# polarshield3_0e.net
KiCad netlist of a schematic drawn in EAGLE
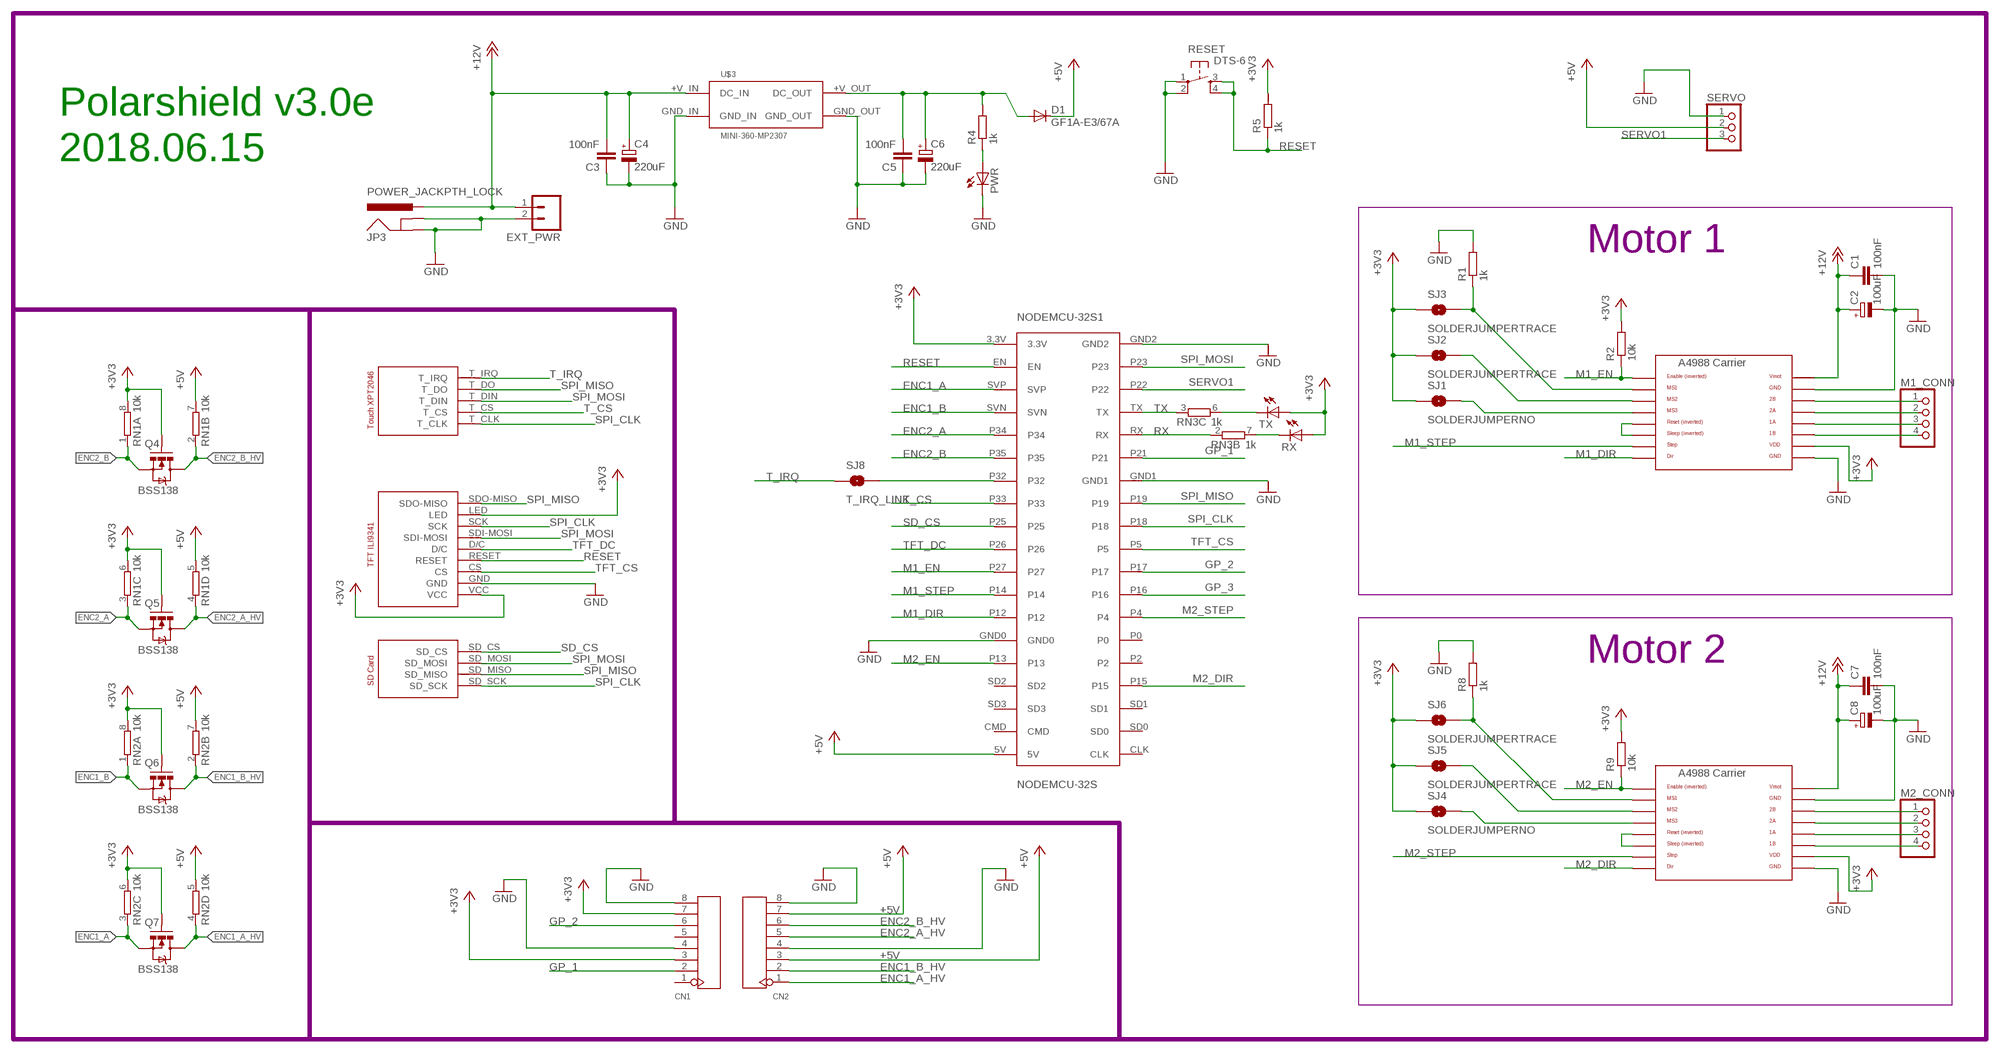
[diagram p0: schematic, sheet 1]

(export (version "E")
  (design (tool "Eeschema 10.0.6"))
  (components
    (comp (ref "C1")
      (value "100nF")
      (footprint "eagle-import:C0805")
      (libsource (lib "eagle-import") (part "C-EUC0805"))
    )
    (comp (ref "C2")
      (value "100uF")
      (footprint "eagle-import:153CLV-0605")
      (libsource (lib "eagle-import") (part "CPOL-EU153CLV-0605"))
    )
    (comp (ref "C3")
      (value "100nF")
      (footprint "eagle-import:C0805")
      (libsource (lib "eagle-import") (part "C-EUC0805"))
    )
    (comp (ref "C4")
      (value "220uF")
      (footprint "eagle-import:153CLV-0605")
      (libsource (lib "eagle-import") (part "CPOL-EU153CLV-0605"))
    )
    (comp (ref "C5")
      (value "100nF")
      (footprint "eagle-import:C0805")
      (libsource (lib "eagle-import") (part "C-EUC0805"))
    )
    (comp (ref "C6")
      (value "220uF")
      (footprint "eagle-import:153CLV-0605")
      (libsource (lib "eagle-import") (part "CPOL-EU153CLV-0605"))
    )
    (comp (ref "C7")
      (value "100nF")
      (footprint "eagle-import:C0805")
      (libsource (lib "eagle-import") (part "C-EUC0805"))
    )
    (comp (ref "C8")
      (value "100uF")
      (footprint "eagle-import:153CLV-0605")
      (libsource (lib "eagle-import") (part "CPOL-EU153CLV-0605"))
    )
    (comp (ref "CN1")
      (value "DIP-BLACK-FEMALE-HEADER-VERT(8P-2.54)")
      (footprint "eagle-import:H8-2.54")
      (fields (field (name "MPN") "F185-1108A1BSYC1"))
      (libsource (lib "eagle-import") (part "DIP-BLACK-FEMALE-HEADER-VERT(8P-2.54)"))
    )
    (comp (ref "CN2")
      (value "DIP-BLACK-FEMALE-HEADER-VERT(8P-2.54)")
      (footprint "eagle-import:H8-2.54")
      (fields (field (name "MPN") "F185-1108A1BSYC1"))
      (libsource (lib "eagle-import") (part "DIP-BLACK-FEMALE-HEADER-VERT(8P-2.54)"))
    )
    (comp (ref "D1")
      (value "GF1A-E3/67A")
      (footprint "eagle-import:DO214BA")
      (libsource (lib "eagle-import") (part "DIODE-DO214BA"))
    )
    (comp (ref "EXT_PWR")
      (value "M02PTH")
      (footprint "eagle-import:1X02")
      (libsource (lib "eagle-import") (part "M02PTH"))
    )
    (comp (ref "JP3")
      (value "POWER_JACKPTH_LOCK")
      (footprint "eagle-import:POWER_JACK_PTH_LOCK")
      (libsource (lib "eagle-import") (part "POWER_JACKPTH_LOCK"))
    )
    (comp (ref "M1_CONN")
      (value "PINHD-1X4/90")
      (footprint "eagle-import:1X04_90")
      (libsource (lib "eagle-import") (part "PINHD-1X4/90"))
    )
    (comp (ref "M2_CONN")
      (value "PINHD-1X4/90")
      (footprint "eagle-import:1X04_90")
      (libsource (lib "eagle-import") (part "PINHD-1X4/90"))
    )
    (comp (ref "MOTOR_1")
      (value "A4988BREAKOUT")
      (footprint "eagle-import:A4988BREAKOUT")
      (libsource (lib "eagle-import") (part "A4988BREAKOUT"))
    )
    (comp (ref "MOTOR_2")
      (value "A4988BREAKOUT")
      (footprint "eagle-import:A4988BREAKOUT")
      (libsource (lib "eagle-import") (part "A4988BREAKOUT"))
    )
    (comp (ref "NODEMCU-32S1")
      (value "NODEMCU-32S")
      (footprint "eagle-import:NODEMCU-32S")
      (libsource (lib "eagle-import") (part "NODEMCU-32S"))
    )
    (comp (ref "PWR")
      (value "LEDCHIPLED_0805")
      (footprint "eagle-import:CHIPLED_0805")
      (libsource (lib "eagle-import") (part "LEDCHIPLED_0805"))
    )
    (comp (ref "Q4")
      (value "BSS138")
      (footprint "eagle-import:SOT23-3")
      (libsource (lib "eagle-import") (part "MOSFET-NCHANNELSMD"))
    )
    (comp (ref "Q5")
      (value "BSS138")
      (footprint "eagle-import:SOT23-3")
      (libsource (lib "eagle-import") (part "MOSFET-NCHANNELSMD"))
    )
    (comp (ref "Q6")
      (value "BSS138")
      (footprint "eagle-import:SOT23-3")
      (libsource (lib "eagle-import") (part "MOSFET-NCHANNELSMD"))
    )
    (comp (ref "Q7")
      (value "BSS138")
      (footprint "eagle-import:SOT23-3")
      (libsource (lib "eagle-import") (part "MOSFET-NCHANNELSMD"))
    )
    (comp (ref "R1")
      (value "1k")
      (footprint "eagle-import:M0805")
      (libsource (lib "eagle-import") (part "R-EU_M0805"))
    )
    (comp (ref "R2")
      (value "10k")
      (footprint "eagle-import:M0805")
      (libsource (lib "eagle-import") (part "R-EU_M0805"))
    )
    (comp (ref "R4")
      (value "1k")
      (footprint "eagle-import:M0805")
      (libsource (lib "eagle-import") (part "R-EU_M0805"))
    )
    (comp (ref "R5")
      (value "1k")
      (footprint "eagle-import:M0805")
      (libsource (lib "eagle-import") (part "R-EU_M0805"))
    )
    (comp (ref "R8")
      (value "1k")
      (footprint "eagle-import:M0805")
      (libsource (lib "eagle-import") (part "R-EU_M0805"))
    )
    (comp (ref "R9")
      (value "10k")
      (footprint "eagle-import:M0805")
      (libsource (lib "eagle-import") (part "R-EU_M0805"))
    )
    (comp (ref "RESET")
      (value "DTS-6")
      (footprint "eagle-import:DTS-6")
      (libsource (lib "eagle-import") (part "DTS-6"))
    )
    (comp (ref "RN1")
      (value "10k")
      (footprint "eagle-import:EXB38V")
      (libsource (lib "eagle-import") (part "4R-NEXB38V"))
    )
    (comp (ref "RN2")
      (value "10k")
      (footprint "eagle-import:EXB38V")
      (libsource (lib "eagle-import") (part "4R-NEXB38V"))
    )
    (comp (ref "RN3")
      (value "1k")
      (footprint "eagle-import:EXB38V")
      (libsource (lib "eagle-import") (part "4R-NEXB38V"))
    )
    (comp (ref "RX")
      (value "LEDCHIPLED_0805")
      (footprint "eagle-import:CHIPLED_0805")
      (libsource (lib "eagle-import") (part "LEDCHIPLED_0805"))
    )
    (comp (ref "SERVO")
      (value "PINHD-1X3/90")
      (footprint "eagle-import:1X03_90")
      (libsource (lib "eagle-import") (part "PINHD-1X3/90"))
    )
    (comp (ref "SJ1")
      (value "SOLDERJUMPERNO")
      (footprint "eagle-import:SJ_2S-NO")
      (libsource (lib "eagle-import") (part "polargraph3_SOLDERJUMPERNO"))
    )
    (comp (ref "SJ2")
      (value "SOLDERJUMPERTRACE")
      (footprint "eagle-import:SJ_2S-TRACE")
      (libsource (lib "eagle-import") (part "polargraph3_SOLDERJUMPERTRACE"))
    )
    (comp (ref "SJ3")
      (value "SOLDERJUMPERTRACE")
      (footprint "eagle-import:SJ_2S-TRACE")
      (libsource (lib "eagle-import") (part "polargraph3_SOLDERJUMPERTRACE"))
    )
    (comp (ref "SJ4")
      (value "SOLDERJUMPERNO")
      (footprint "eagle-import:SJ_2S-NO")
      (libsource (lib "eagle-import") (part "polargraph3_SOLDERJUMPERNO"))
    )
    (comp (ref "SJ5")
      (value "SOLDERJUMPERTRACE")
      (footprint "eagle-import:SJ_2S-TRACE")
      (libsource (lib "eagle-import") (part "polargraph3_SOLDERJUMPERTRACE"))
    )
    (comp (ref "SJ6")
      (value "SOLDERJUMPERTRACE")
      (footprint "eagle-import:SJ_2S-TRACE")
      (libsource (lib "eagle-import") (part "polargraph3_SOLDERJUMPERTRACE"))
    )
    (comp (ref "SJ8")
      (value "T_IRQ_LINK")
      (footprint "eagle-import:SJ_2S-NO")
      (libsource (lib "eagle-import") (part "SOLDERJUMPERNO"))
    )
    (comp (ref "TX")
      (value "LEDCHIPLED_0805")
      (footprint "eagle-import:CHIPLED_0805")
      (libsource (lib "eagle-import") (part "LEDCHIPLED_0805"))
    )
    (comp (ref "U$2")
      (value "2.4_TFT_SPI_TOUCH_SD")
      (footprint "eagle-import:2.4_TFT_SPI_TOUCH_SD")
      (libsource (lib "eagle-import") (part "2.4_TFT_SPI_TOUCH_SD"))
    )
    (comp (ref "U$3")
      (value "MINI-360-MP2307")
      (footprint "eagle-import:MINI-360-MP2307")
      (libsource (lib "eagle-import") (part "MINI-360-MP2307"))
    )
  )
  (nets
    (net (code "1") (name "+3V3") (class "Default")
      (node (ref "CN1") (pin "3") (pinfunction "3_3") (pintype "bidirectional"))
      (node (ref "CN1") (pin "7") (pinfunction "7_7") (pintype "bidirectional"))
      (node (ref "MOTOR_1") (pin "VDD") (pinfunction "VDD_VDD") (pintype "power_in"))
      (node (ref "MOTOR_2") (pin "VDD") (pinfunction "VDD_VDD") (pintype "power_in"))
      (node (ref "NODEMCU-32S1") (pin "3.3V") (pinfunction "3.3V_3.3V") (pintype "bidirectional"))
      (node (ref "Q4") (pin "1") (pinfunction "G_1") (pintype "passive"))
      (node (ref "Q5") (pin "1") (pinfunction "G_1") (pintype "passive"))
      (node (ref "Q6") (pin "1") (pinfunction "G_1") (pintype "passive"))
      (node (ref "Q7") (pin "1") (pinfunction "G_1") (pintype "passive"))
      (node (ref "R2") (pin "2") (pinfunction "2_2") (pintype "passive"))
      (node (ref "R5") (pin "2") (pinfunction "2_2") (pintype "passive"))
      (node (ref "R9") (pin "2") (pinfunction "2_2") (pintype "passive"))
      (node (ref "RN1") (pin "6") (pinfunction "2_6") (pintype "passive"))
      (node (ref "RN1") (pin "8") (pinfunction "2_8") (pintype "passive"))
      (node (ref "RN2") (pin "6") (pinfunction "2_6") (pintype "passive"))
      (node (ref "RN2") (pin "8") (pinfunction "2_8") (pintype "passive"))
      (node (ref "RX") (pin "A") (pinfunction "A_A") (pintype "passive"))
      (node (ref "SJ1") (pin "1") (pinfunction "1_1") (pintype "passive"))
      (node (ref "SJ2") (pin "1") (pinfunction "1_1") (pintype "passive"))
      (node (ref "SJ3") (pin "1") (pinfunction "1_1") (pintype "passive"))
      (node (ref "SJ4") (pin "1") (pinfunction "1_1") (pintype "passive"))
      (node (ref "SJ5") (pin "1") (pinfunction "1_1") (pintype "passive"))
      (node (ref "SJ6") (pin "1") (pinfunction "1_1") (pintype "passive"))
      (node (ref "TX") (pin "A") (pinfunction "A_A") (pintype "passive"))
      (node (ref "U$2") (pin "LED") (pinfunction "LED_LED") (pintype "bidirectional"))
      (node (ref "U$2") (pin "VCC") (pinfunction "VCC_VCC") (pintype "bidirectional"))
    )
    (net (code "2") (name "+5V") (class "Default")
      (node (ref "CN2") (pin "3") (pinfunction "3_3") (pintype "bidirectional"))
      (node (ref "CN2") (pin "7") (pinfunction "7_7") (pintype "bidirectional"))
      (node (ref "D1") (pin "C") (pinfunction "C_C") (pintype "passive"))
      (node (ref "NODEMCU-32S1") (pin "5V") (pinfunction "5V_5V") (pintype "bidirectional"))
      (node (ref "RN1") (pin "5") (pinfunction "2_5") (pintype "passive"))
      (node (ref "RN1") (pin "7") (pinfunction "2_7") (pintype "passive"))
      (node (ref "RN2") (pin "5") (pinfunction "2_5") (pintype "passive"))
      (node (ref "RN2") (pin "7") (pinfunction "2_7") (pintype "passive"))
      (node (ref "SERVO") (pin "2") (pinfunction "2_2") (pintype "passive"))
    )
    (net (code "3") (name "+12V") (class "Default")
      (node (ref "C1") (pin "1") (pinfunction "1_1") (pintype "passive"))
      (node (ref "C2") (pin "+") (pinfunction "+_+") (pintype "passive"))
      (node (ref "C3") (pin "2") (pinfunction "2_2") (pintype "passive"))
      (node (ref "C4") (pin "+") (pinfunction "+_+") (pintype "passive"))
      (node (ref "C7") (pin "1") (pinfunction "1_1") (pintype "passive"))
      (node (ref "C8") (pin "+") (pinfunction "+_+") (pintype "passive"))
      (node (ref "EXT_PWR") (pin "1") (pinfunction "1_1") (pintype "passive"))
      (node (ref "JP3") (pin "PWR") (pinfunction "PWR_PWR") (pintype "bidirectional"))
      (node (ref "MOTOR_1") (pin "VMOT") (pinfunction "VMOT_VMOT") (pintype "power_in"))
      (node (ref "MOTOR_2") (pin "VMOT") (pinfunction "VMOT_VMOT") (pintype "power_in"))
      (node (ref "U$3") (pin "+V_IN") (pinfunction "DC_IN_+V_IN") (pintype "bidirectional"))
    )
    (net (code "4") (name "/GP_1") (class "Default")
      (node (ref "CN1") (pin "2") (pinfunction "2_2") (pintype "bidirectional"))
      (node (ref "NODEMCU-32S1") (pin "P21") (pinfunction "P21_P21") (pintype "bidirectional"))
    )
    (net (code "5") (name "/GP_2") (class "Default")
      (node (ref "CN1") (pin "6") (pinfunction "6_6") (pintype "bidirectional"))
      (node (ref "NODEMCU-32S1") (pin "P17") (pinfunction "P17_P17") (pintype "bidirectional"))
    )
    (net (code "6") (name "/GP_3") (class "Default")
      (node (ref "NODEMCU-32S1") (pin "P16") (pinfunction "P16_P16") (pintype "bidirectional"))
    )
    (net (code "7") (name "/M1_DIR") (class "Default")
      (node (ref "MOTOR_1") (pin "DIR") (pinfunction "DIR_DIR") (pintype "input"))
      (node (ref "NODEMCU-32S1") (pin "P12") (pinfunction "P12_P12") (pintype "bidirectional"))
    )
    (net (code "8") (name "/M1_EN") (class "Default")
      (node (ref "MOTOR_1") (pin "EN") (pinfunction "EN_EN") (pintype "input"))
      (node (ref "NODEMCU-32S1") (pin "P27") (pinfunction "P27_P27") (pintype "bidirectional"))
      (node (ref "R2") (pin "1") (pinfunction "1_1") (pintype "passive"))
    )
    (net (code "9") (name "/M1_STEP") (class "Default")
      (node (ref "MOTOR_1") (pin "STEP") (pinfunction "STEP_STEP") (pintype "input"))
      (node (ref "NODEMCU-32S1") (pin "P14") (pinfunction "P14_P14") (pintype "bidirectional"))
    )
    (net (code "10") (name "/M2_DIR") (class "Default")
      (node (ref "MOTOR_2") (pin "DIR") (pinfunction "DIR_DIR") (pintype "input"))
      (node (ref "NODEMCU-32S1") (pin "P15") (pinfunction "P15_P15") (pintype "bidirectional"))
    )
    (net (code "11") (name "/M2_EN") (class "Default")
      (node (ref "MOTOR_2") (pin "EN") (pinfunction "EN_EN") (pintype "input"))
      (node (ref "NODEMCU-32S1") (pin "P13") (pinfunction "P13_P13") (pintype "bidirectional"))
      (node (ref "R9") (pin "1") (pinfunction "1_1") (pintype "passive"))
    )
    (net (code "12") (name "/M2_STEP") (class "Default")
      (node (ref "MOTOR_2") (pin "STEP") (pinfunction "STEP_STEP") (pintype "input"))
      (node (ref "NODEMCU-32S1") (pin "P4") (pinfunction "P4_P4") (pintype "bidirectional"))
    )
    (net (code "13") (name "/RESET") (class "Default")
      (node (ref "NODEMCU-32S1") (pin "EN") (pinfunction "EN_EN") (pintype "bidirectional"))
      (node (ref "R5") (pin "1") (pinfunction "1_1") (pintype "passive"))
      (node (ref "RESET") (pin "3") (pinfunction "3_3") (pintype "passive"))
      (node (ref "RESET") (pin "4") (pinfunction "4_4") (pintype "passive"))
      (node (ref "U$2") (pin "RESET") (pinfunction "RESET_RESET") (pintype "bidirectional"))
    )
    (net (code "14") (name "/RX") (class "Default")
      (node (ref "NODEMCU-32S1") (pin "RX") (pinfunction "RX_RX") (pintype "bidirectional"))
      (node (ref "RN3") (pin "2") (pinfunction "1_2") (pintype "passive"))
    )
    (net (code "15") (name "/SD_CS") (class "Default")
      (node (ref "NODEMCU-32S1") (pin "P25") (pinfunction "P25_P25") (pintype "bidirectional"))
      (node (ref "U$2") (pin "SD_CS") (pinfunction "SD_CS_SD_CS") (pintype "bidirectional"))
    )
    (net (code "16") (name "/SERVO1") (class "Default")
      (node (ref "NODEMCU-32S1") (pin "P22") (pinfunction "P22_P22") (pintype "bidirectional"))
      (node (ref "SERVO") (pin "3") (pinfunction "3_3") (pintype "passive"))
    )
    (net (code "17") (name "/SPI_CLK") (class "Default")
      (node (ref "NODEMCU-32S1") (pin "P18") (pinfunction "P18_P18") (pintype "bidirectional"))
      (node (ref "U$2") (pin "SCK") (pinfunction "SCK_SCK") (pintype "bidirectional"))
      (node (ref "U$2") (pin "SD_SCK") (pinfunction "SD_SCK_SD_SCK") (pintype "bidirectional"))
      (node (ref "U$2") (pin "T_CLK") (pinfunction "T_CLK_T_CLK") (pintype "input"))
    )
    (net (code "18") (name "/SPI_MISO") (class "Default")
      (node (ref "NODEMCU-32S1") (pin "P19") (pinfunction "P19_P19") (pintype "bidirectional"))
      (node (ref "U$2") (pin "SDO-MISO") (pinfunction "SDO-MISO_SDO-MISO") (pintype "bidirectional"))
      (node (ref "U$2") (pin "SD_MISO") (pinfunction "SD_MISO_SD_MISO") (pintype "bidirectional"))
      (node (ref "U$2") (pin "T_DO") (pinfunction "T_DO_T_DO") (pintype "output"))
    )
    (net (code "19") (name "/SPI_MOSI") (class "Default")
      (node (ref "NODEMCU-32S1") (pin "P23") (pinfunction "P23_P23") (pintype "bidirectional"))
      (node (ref "U$2") (pin "SDI-MOSI") (pinfunction "SDI-MOSI_SDI-MOSI") (pintype "bidirectional"))
      (node (ref "U$2") (pin "SD_MOSI") (pinfunction "SD_MOSI_SD_MOSI") (pintype "bidirectional"))
      (node (ref "U$2") (pin "T_DIN") (pinfunction "T_DIN_T_DIN") (pintype "input"))
    )
    (net (code "20") (name "/TFT_CS") (class "Default")
      (node (ref "NODEMCU-32S1") (pin "P5") (pinfunction "P5_P5") (pintype "bidirectional"))
      (node (ref "U$2") (pin "CS") (pinfunction "CS_CS") (pintype "bidirectional"))
    )
    (net (code "21") (name "/TFT_DC") (class "Default")
      (node (ref "NODEMCU-32S1") (pin "P26") (pinfunction "P26_P26") (pintype "bidirectional"))
      (node (ref "U$2") (pin "D/C") (pinfunction "D/C_D/C") (pintype "bidirectional"))
    )
    (net (code "22") (name "/TX") (class "Default")
      (node (ref "NODEMCU-32S1") (pin "TX") (pinfunction "TX_TX") (pintype "bidirectional"))
      (node (ref "RN3") (pin "3") (pinfunction "1_3") (pintype "passive"))
    )
    (net (code "23") (name "/T_CS") (class "Default")
      (node (ref "NODEMCU-32S1") (pin "P33") (pinfunction "P33_P33") (pintype "bidirectional"))
      (node (ref "U$2") (pin "T_CS") (pinfunction "T_CS_T_CS") (pintype "output"))
    )
    (net (code "24") (name "/T_IRQ") (class "Default")
      (node (ref "SJ8") (pin "1") (pinfunction "1_1") (pintype "passive"))
      (node (ref "U$2") (pin "T_IRQ") (pinfunction "T_IRQ_T_IRQ") (pintype "output"))
    )
    (net (code "25") (name "ENC1_A") (class "Default")
      (node (ref "NODEMCU-32S1") (pin "SVP") (pinfunction "SVP_SVP") (pintype "bidirectional"))
      (node (ref "Q7") (pin "2") (pinfunction "S_2") (pintype "passive"))
      (node (ref "RN2") (pin "3") (pinfunction "1_3") (pintype "passive"))
    )
    (net (code "26") (name "ENC1_A_HV") (class "Default")
      (node (ref "CN2") (pin "1") (pinfunction "1_1") (pintype "bidirectional"))
      (node (ref "Q7") (pin "3") (pinfunction "D_3") (pintype "passive"))
      (node (ref "RN2") (pin "4") (pinfunction "1_4") (pintype "passive"))
    )
    (net (code "27") (name "ENC1_B") (class "Default")
      (node (ref "NODEMCU-32S1") (pin "SVN") (pinfunction "SVN_SVN") (pintype "bidirectional"))
      (node (ref "Q6") (pin "2") (pinfunction "S_2") (pintype "passive"))
      (node (ref "RN2") (pin "1") (pinfunction "1_1") (pintype "passive"))
    )
    (net (code "28") (name "ENC1_B_HV") (class "Default")
      (node (ref "CN2") (pin "2") (pinfunction "2_2") (pintype "bidirectional"))
      (node (ref "Q6") (pin "3") (pinfunction "D_3") (pintype "passive"))
      (node (ref "RN2") (pin "2") (pinfunction "1_2") (pintype "passive"))
    )
    (net (code "29") (name "ENC2_A") (class "Default")
      (node (ref "NODEMCU-32S1") (pin "P34") (pinfunction "P34_P34") (pintype "bidirectional"))
      (node (ref "Q5") (pin "2") (pinfunction "S_2") (pintype "passive"))
      (node (ref "RN1") (pin "3") (pinfunction "1_3") (pintype "passive"))
    )
    (net (code "30") (name "ENC2_A_HV") (class "Default")
      (node (ref "CN2") (pin "5") (pinfunction "5_5") (pintype "bidirectional"))
      (node (ref "Q5") (pin "3") (pinfunction "D_3") (pintype "passive"))
      (node (ref "RN1") (pin "4") (pinfunction "1_4") (pintype "passive"))
    )
    (net (code "31") (name "ENC2_B") (class "Default")
      (node (ref "NODEMCU-32S1") (pin "P35") (pinfunction "P35_P35") (pintype "bidirectional"))
      (node (ref "Q4") (pin "2") (pinfunction "S_2") (pintype "passive"))
      (node (ref "RN1") (pin "1") (pinfunction "1_1") (pintype "passive"))
    )
    (net (code "32") (name "ENC2_B_HV") (class "Default")
      (node (ref "CN2") (pin "6") (pinfunction "6_6") (pintype "bidirectional"))
      (node (ref "Q4") (pin "3") (pinfunction "D_3") (pintype "passive"))
      (node (ref "RN1") (pin "2") (pinfunction "1_2") (pintype "passive"))
    )
    (net (code "33") (name "GND") (class "Default")
      (node (ref "C1") (pin "2") (pinfunction "2_2") (pintype "passive"))
      (node (ref "C2") (pin "-") (pinfunction "-_-") (pintype "passive"))
      (node (ref "C3") (pin "1") (pinfunction "1_1") (pintype "passive"))
      (node (ref "C4") (pin "-") (pinfunction "-_-") (pintype "passive"))
      (node (ref "C5") (pin "1") (pinfunction "1_1") (pintype "passive"))
      (node (ref "C6") (pin "-") (pinfunction "-_-") (pintype "passive"))
      (node (ref "C7") (pin "2") (pinfunction "2_2") (pintype "passive"))
      (node (ref "C8") (pin "-") (pinfunction "-_-") (pintype "passive"))
      (node (ref "CN1") (pin "4") (pinfunction "4_4") (pintype "bidirectional"))
      (node (ref "CN1") (pin "8") (pinfunction "8_8") (pintype "bidirectional"))
      (node (ref "CN2") (pin "4") (pinfunction "4_4") (pintype "bidirectional"))
      (node (ref "CN2") (pin "8") (pinfunction "8_8") (pintype "bidirectional"))
      (node (ref "EXT_PWR") (pin "2") (pinfunction "2_2") (pintype "passive"))
      (node (ref "JP3") (pin "GND") (pinfunction "GND_GND") (pintype "bidirectional"))
      (node (ref "JP3") (pin "GNDBREAK") (pinfunction "GNDBREAK_GNDBREAK") (pintype "bidirectional"))
      (node (ref "MOTOR_1") (pin "GND") (pinfunction "GND_GND") (pintype "power_in"))
      (node (ref "MOTOR_1") (pin "GND@0") (pinfunction "GND_GND@0") (pintype "power_in"))
      (node (ref "MOTOR_2") (pin "GND") (pinfunction "GND_GND") (pintype "power_in"))
      (node (ref "MOTOR_2") (pin "GND@0") (pinfunction "GND_GND@0") (pintype "power_in"))
      (node (ref "NODEMCU-32S1") (pin "GND0") (pinfunction "GND0_GND0") (pintype "bidirectional"))
      (node (ref "NODEMCU-32S1") (pin "GND1") (pinfunction "GND1_GND1") (pintype "bidirectional"))
      (node (ref "NODEMCU-32S1") (pin "GND2") (pinfunction "GND2_GND2") (pintype "bidirectional"))
      (node (ref "PWR") (pin "C") (pinfunction "C_C") (pintype "passive"))
      (node (ref "R1") (pin "2") (pinfunction "2_2") (pintype "passive"))
      (node (ref "R8") (pin "2") (pinfunction "2_2") (pintype "passive"))
      (node (ref "RESET") (pin "1") (pinfunction "1_1") (pintype "passive"))
      (node (ref "RESET") (pin "2") (pinfunction "2_2") (pintype "passive"))
      (node (ref "SERVO") (pin "1") (pinfunction "1_1") (pintype "passive"))
      (node (ref "U$2") (pin "GND") (pinfunction "GND_GND") (pintype "bidirectional"))
      (node (ref "U$3") (pin "GND_IN") (pinfunction "GND_IN_GND_IN") (pintype "bidirectional"))
      (node (ref "U$3") (pin "GND_OUT") (pinfunction "GND_OUT_GND_OUT") (pintype "bidirectional"))
    )
    (net (code "34") (name "Net-(M1_CONN-Pad1)") (class "Default")
      (node (ref "M1_CONN") (pin "1") (pinfunction "1_1") (pintype "passive"))
      (node (ref "MOTOR_1") (pin "2B") (pinfunction "2B_2B") (pintype "output"))
    )
    (net (code "35") (name "Net-(M1_CONN-Pad2)") (class "Default")
      (node (ref "M1_CONN") (pin "2") (pinfunction "2_2") (pintype "passive"))
      (node (ref "MOTOR_1") (pin "2A") (pinfunction "2A_2A") (pintype "output"))
    )
    (net (code "36") (name "Net-(M1_CONN-Pad3)") (class "Default")
      (node (ref "M1_CONN") (pin "3") (pinfunction "3_3") (pintype "passive"))
      (node (ref "MOTOR_1") (pin "1A") (pinfunction "1A_1A") (pintype "output"))
    )
    (net (code "37") (name "Net-(M1_CONN-Pad4)") (class "Default")
      (node (ref "M1_CONN") (pin "4") (pinfunction "4_4") (pintype "passive"))
      (node (ref "MOTOR_1") (pin "1B") (pinfunction "1B_1B") (pintype "output"))
    )
    (net (code "38") (name "Net-(M2_CONN-Pad1)") (class "Default")
      (node (ref "M2_CONN") (pin "1") (pinfunction "1_1") (pintype "passive"))
      (node (ref "MOTOR_2") (pin "2B") (pinfunction "2B_2B") (pintype "output"))
    )
    (net (code "39") (name "Net-(M2_CONN-Pad2)") (class "Default")
      (node (ref "M2_CONN") (pin "2") (pinfunction "2_2") (pintype "passive"))
      (node (ref "MOTOR_2") (pin "2A") (pinfunction "2A_2A") (pintype "output"))
    )
    (net (code "40") (name "Net-(M2_CONN-Pad3)") (class "Default")
      (node (ref "M2_CONN") (pin "3") (pinfunction "3_3") (pintype "passive"))
      (node (ref "MOTOR_2") (pin "1A") (pinfunction "1A_1A") (pintype "output"))
    )
    (net (code "41") (name "Net-(M2_CONN-Pad4)") (class "Default")
      (node (ref "M2_CONN") (pin "4") (pinfunction "4_4") (pintype "passive"))
      (node (ref "MOTOR_2") (pin "1B") (pinfunction "1B_1B") (pintype "output"))
    )
    (net (code "42") (name "Net-(MOTOR_1-PadMS1)") (class "Default")
      (node (ref "MOTOR_1") (pin "MS1") (pinfunction "MS1_MS1") (pintype "input"))
      (node (ref "R1") (pin "1") (pinfunction "1_1") (pintype "passive"))
      (node (ref "SJ3") (pin "2") (pinfunction "2_2") (pintype "passive"))
    )
    (net (code "43") (name "Net-(MOTOR_1-PadMS2)") (class "Default")
      (node (ref "MOTOR_1") (pin "MS2") (pinfunction "MS2_MS2") (pintype "input"))
      (node (ref "SJ2") (pin "2") (pinfunction "2_2") (pintype "passive"))
    )
    (net (code "44") (name "Net-(MOTOR_1-PadMS3)") (class "Default")
      (node (ref "MOTOR_1") (pin "MS3") (pinfunction "MS3_MS3") (pintype "input"))
      (node (ref "SJ1") (pin "2") (pinfunction "2_2") (pintype "passive"))
    )
    (net (code "45") (name "Net-(MOTOR_1-SLEEP)") (class "Default")
      (node (ref "MOTOR_1") (pin "RST") (pinfunction "RST_RST") (pintype "input"))
      (node (ref "MOTOR_1") (pin "SLP") (pinfunction "SLEEP_SLP") (pintype "input"))
    )
    (net (code "46") (name "Net-(MOTOR_2-PadMS1)") (class "Default")
      (node (ref "MOTOR_2") (pin "MS1") (pinfunction "MS1_MS1") (pintype "input"))
      (node (ref "R8") (pin "1") (pinfunction "1_1") (pintype "passive"))
      (node (ref "SJ6") (pin "2") (pinfunction "2_2") (pintype "passive"))
    )
    (net (code "47") (name "Net-(MOTOR_2-PadMS2)") (class "Default")
      (node (ref "MOTOR_2") (pin "MS2") (pinfunction "MS2_MS2") (pintype "input"))
      (node (ref "SJ5") (pin "2") (pinfunction "2_2") (pintype "passive"))
    )
    (net (code "48") (name "Net-(MOTOR_2-PadMS3)") (class "Default")
      (node (ref "MOTOR_2") (pin "MS3") (pinfunction "MS3_MS3") (pintype "input"))
      (node (ref "SJ4") (pin "2") (pinfunction "2_2") (pintype "passive"))
    )
    (net (code "49") (name "Net-(MOTOR_2-SLEEP)") (class "Default")
      (node (ref "MOTOR_2") (pin "RST") (pinfunction "RST_RST") (pintype "input"))
      (node (ref "MOTOR_2") (pin "SLP") (pinfunction "SLEEP_SLP") (pintype "input"))
    )
    (net (code "50") (name "Net-(NODEMCU-32S1-PadP32)") (class "Default")
      (node (ref "NODEMCU-32S1") (pin "P32") (pinfunction "P32_P32") (pintype "bidirectional"))
      (node (ref "SJ8") (pin "2") (pinfunction "2_2") (pintype "passive"))
    )
    (net (code "51") (name "Net-(PWR-PadA)") (class "Default")
      (node (ref "PWR") (pin "A") (pinfunction "A_A") (pintype "passive"))
      (node (ref "R4") (pin "1") (pinfunction "1_1") (pintype "passive"))
    )
    (net (code "52") (name "Net-(RN3B-2)") (class "Default")
      (node (ref "RN3") (pin "7") (pinfunction "2_7") (pintype "passive"))
      (node (ref "RX") (pin "C") (pinfunction "C_C") (pintype "passive"))
    )
    (net (code "53") (name "Net-(RN3C-2)") (class "Default")
      (node (ref "RN3") (pin "6") (pinfunction "2_6") (pintype "passive"))
      (node (ref "TX") (pin "C") (pinfunction "C_C") (pintype "passive"))
    )
    (net (code "54") (name "Net-(U$3-DC_OUT)") (class "Default")
      (node (ref "C5") (pin "2") (pinfunction "2_2") (pintype "passive"))
      (node (ref "C6") (pin "+") (pinfunction "+_+") (pintype "passive"))
      (node (ref "D1") (pin "A") (pinfunction "A_A") (pintype "passive"))
      (node (ref "R4") (pin "2") (pinfunction "2_2") (pintype "passive"))
      (node (ref "U$3") (pin "+V_OUT") (pinfunction "DC_OUT_+V_OUT") (pintype "bidirectional"))
    )
    (net (code "55") (name "unconnected-(CN1-Pad1)") (class "Default")
      (node (ref "CN1") (pin "1") (pinfunction "1_1") (pintype "bidirectional"))
    )
    (net (code "56") (name "unconnected-(CN1-Pad5)") (class "Default")
      (node (ref "CN1") (pin "5") (pinfunction "5_5") (pintype "bidirectional"))
    )
    (net (code "57") (name "unconnected-(NODEMCU-32S1-PadCLK)") (class "Default")
      (node (ref "NODEMCU-32S1") (pin "CLK") (pinfunction "CLK_CLK") (pintype "bidirectional"))
    )
    (net (code "58") (name "unconnected-(NODEMCU-32S1-PadCMD)") (class "Default")
      (node (ref "NODEMCU-32S1") (pin "CMD") (pinfunction "CMD_CMD") (pintype "bidirectional"))
    )
    (net (code "59") (name "unconnected-(NODEMCU-32S1-PadP0)") (class "Default")
      (node (ref "NODEMCU-32S1") (pin "P0") (pinfunction "P0_P0") (pintype "bidirectional"))
    )
    (net (code "60") (name "unconnected-(NODEMCU-32S1-PadP2)") (class "Default")
      (node (ref "NODEMCU-32S1") (pin "P2") (pinfunction "P2_P2") (pintype "bidirectional"))
    )
    (net (code "61") (name "unconnected-(NODEMCU-32S1-PadSD0)") (class "Default")
      (node (ref "NODEMCU-32S1") (pin "SD0") (pinfunction "SD0_SD0") (pintype "bidirectional"))
    )
    (net (code "62") (name "unconnected-(NODEMCU-32S1-PadSD1)") (class "Default")
      (node (ref "NODEMCU-32S1") (pin "SD1") (pinfunction "SD1_SD1") (pintype "bidirectional"))
    )
    (net (code "63") (name "unconnected-(NODEMCU-32S1-PadSD2)") (class "Default")
      (node (ref "NODEMCU-32S1") (pin "SD2") (pinfunction "SD2_SD2") (pintype "bidirectional"))
    )
    (net (code "64") (name "unconnected-(NODEMCU-32S1-PadSD3)") (class "Default")
      (node (ref "NODEMCU-32S1") (pin "SD3") (pinfunction "SD3_SD3") (pintype "bidirectional"))
    )
  )
)
